# OSO-MISC-21-015_Temperature_and_Light_Bo.net
KiCad netlist of a schematic drawn in EAGLE
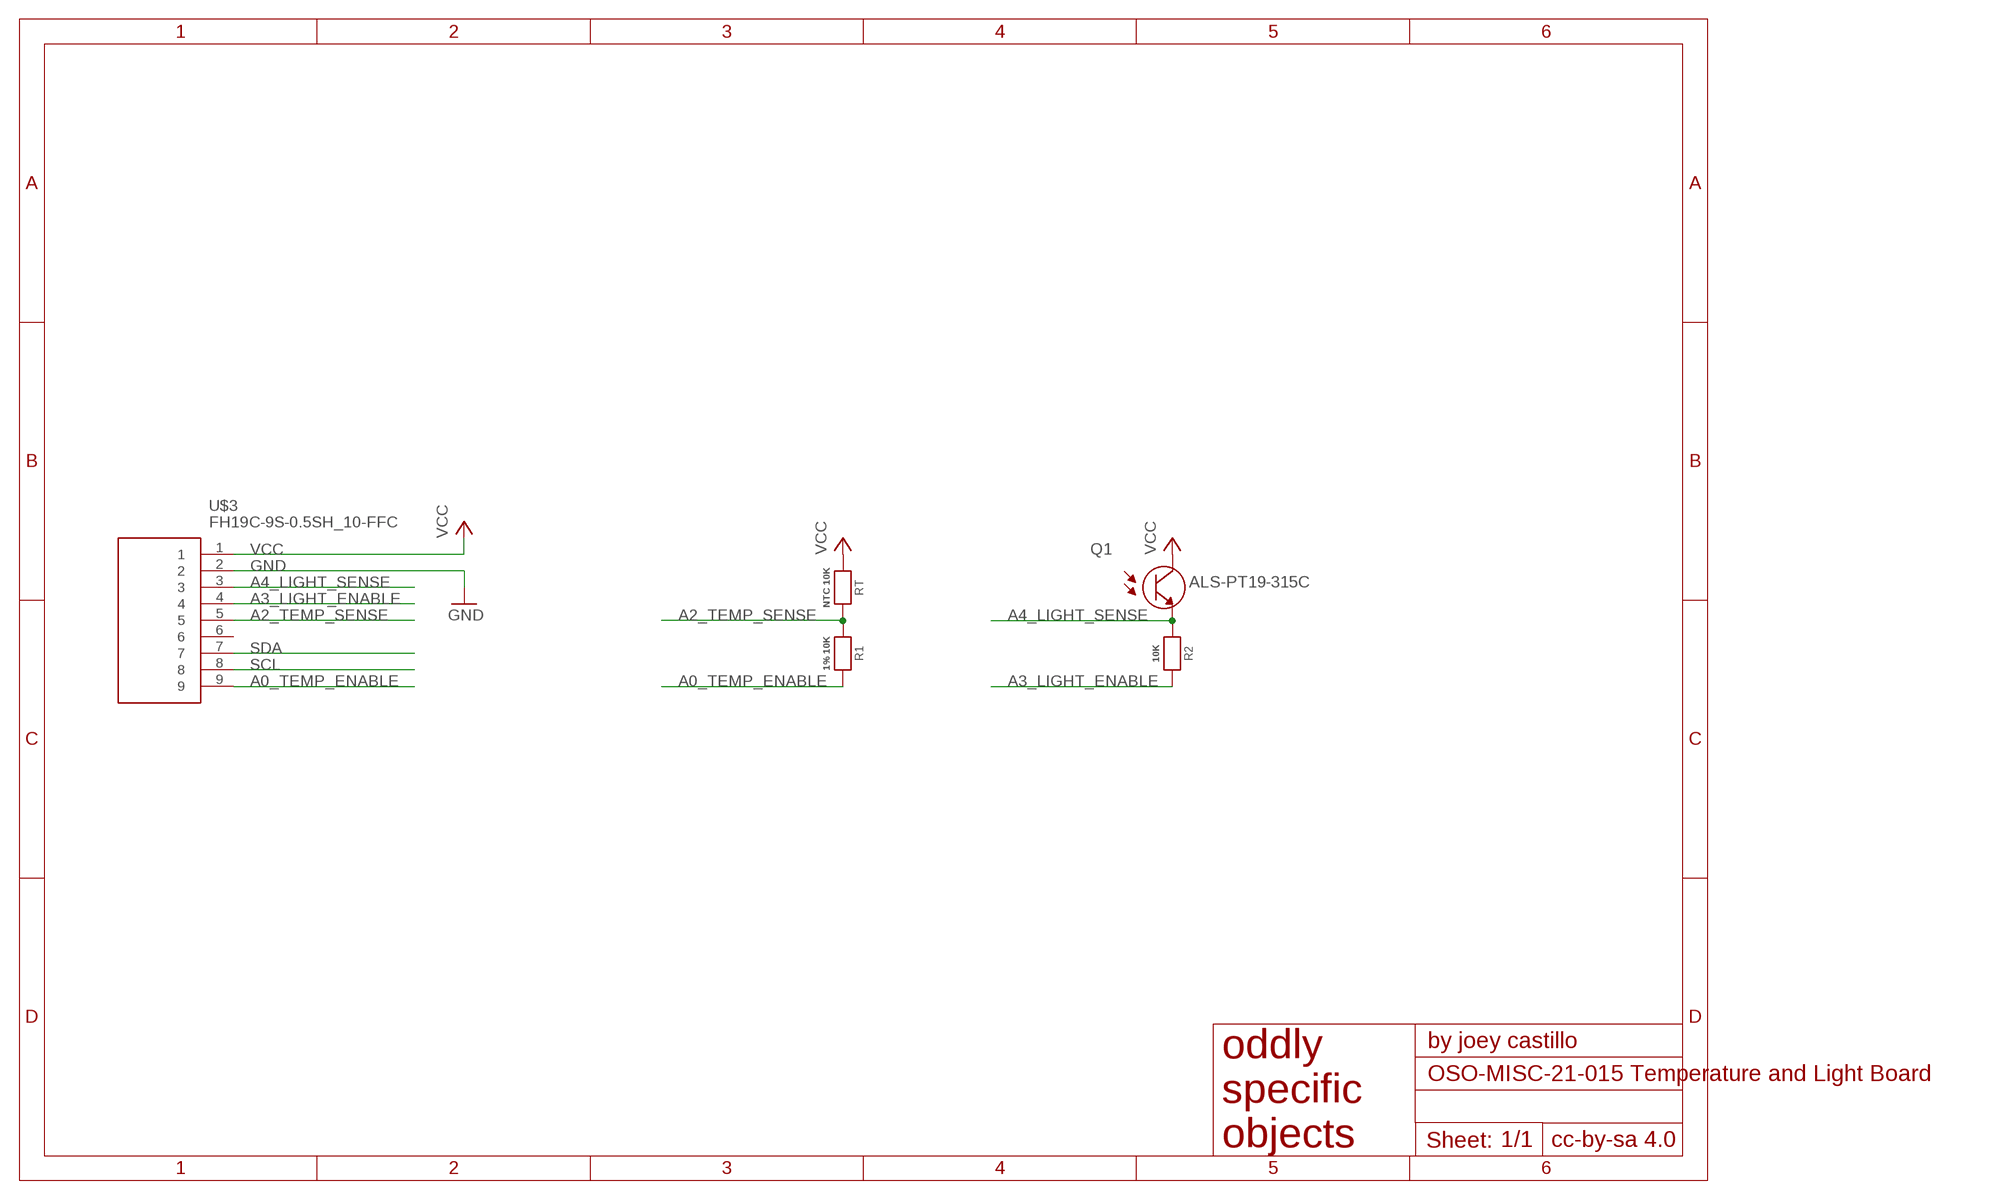
[diagram p0: schematic, sheet 1]

(export (version "E")
  (design (tool "Eeschema 10.0.6"))
  (components
    (comp (ref "Q1")
      (value "ALS-PT19-315C")
      (footprint "eagle-import:XDCR_ALS-PT19-315C_L177_TR8_REVERSE")
      (libsource (lib "eagle-import") (part "ALS-PT19-315C/L177/TR8REVERSEMOUNT"))
    )
    (comp (ref "R1")
      (value "1% 10K")
      (footprint "eagle-import:_0603MP")
      (libsource (lib "eagle-import") (part "RESISTOR_0603MP"))
    )
    (comp (ref "R2")
      (value "10K")
      (footprint "eagle-import:_0603MP")
      (libsource (lib "eagle-import") (part "RESISTOR_0603MP"))
    )
    (comp (ref "RT")
      (value "NTC 10K")
      (footprint "eagle-import:_0603")
      (libsource (lib "eagle-import") (part "RESISTOR_0603"))
    )
    (comp (ref "U$3")
      (value "FH19C-9S-0.5SH_10-FFC")
      (footprint "eagle-import:FH19C9S05SH10-FFC")
      (libsource (lib "eagle-import") (part "FH19C-9S-0.5SH_10-FFC"))
    )
  )
  (nets
    (net (code "1") (name "/A0_TEMP_ENABLE") (class "Default")
      (node (ref "R1") (pin "2") (pinfunction "2_2") (pintype "passive"))
      (node (ref "U$3") (pin "9") (pinfunction "9_9") (pintype "bidirectional"))
    )
    (net (code "2") (name "/A2_TEMP_SENSE") (class "Default")
      (node (ref "R1") (pin "1") (pinfunction "1_1") (pintype "passive"))
      (node (ref "RT") (pin "2") (pinfunction "2_2") (pintype "passive"))
      (node (ref "U$3") (pin "5") (pinfunction "5_5") (pintype "bidirectional"))
    )
    (net (code "3") (name "/A3_LIGHT_ENABLE") (class "Default")
      (node (ref "R2") (pin "2") (pinfunction "2_2") (pintype "passive"))
      (node (ref "U$3") (pin "4") (pinfunction "4_4") (pintype "bidirectional"))
    )
    (net (code "4") (name "/A4_LIGHT_SENSE") (class "Default")
      (node (ref "Q1") (pin "2") (pinfunction "E_2") (pintype "passive"))
      (node (ref "R2") (pin "1") (pinfunction "1_1") (pintype "passive"))
      (node (ref "U$3") (pin "3") (pinfunction "3_3") (pintype "bidirectional"))
    )
    (net (code "5") (name "/SCL") (class "Default")
      (node (ref "U$3") (pin "8") (pinfunction "8_8") (pintype "bidirectional"))
    )
    (net (code "6") (name "/SDA") (class "Default")
      (node (ref "U$3") (pin "7") (pinfunction "7_7") (pintype "bidirectional"))
    )
    (net (code "7") (name "GND") (class "Default")
      (node (ref "U$3") (pin "2") (pinfunction "2_2") (pintype "bidirectional"))
    )
    (net (code "8") (name "VCC") (class "Default")
      (node (ref "Q1") (pin "1") (pinfunction "C_1") (pintype "passive"))
      (node (ref "RT") (pin "1") (pinfunction "1_1") (pintype "passive"))
      (node (ref "U$3") (pin "1") (pinfunction "1_1") (pintype "bidirectional"))
    )
    (net (code "9") (name "unconnected-(U$3-Pad6)") (class "Default")
      (node (ref "U$3") (pin "6") (pinfunction "6_6") (pintype "bidirectional"))
    )
  )
)
